# R-Split_Level_Shifter_1k_2k.net
KiCad netlist of a schematic drawn in EAGLE
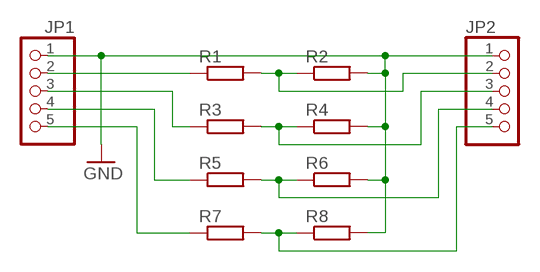
[diagram p0: schematic, sheet 1]

(export (version "E")
  (design (tool "Eeschema 10.0.6"))
  (components
    (comp (ref "JP1")
      (value "PINHD-1X5")
      (footprint "eagle-import:1X05")
      (libsource (lib "eagle-import") (part "PINHD-1X5"))
    )
    (comp (ref "JP2")
      (value "PINHD-1X5")
      (footprint "eagle-import:1X05")
      (libsource (lib "eagle-import") (part "PINHD-1X5"))
    )
    (comp (ref "R1")
      (value "R-EU_0207/7")
      (footprint "eagle-import:0207_7")
      (libsource (lib "eagle-import") (part "R-EU_0207/7"))
    )
    (comp (ref "R2")
      (value "R-EU_0207/7")
      (footprint "eagle-import:0207_7")
      (libsource (lib "eagle-import") (part "R-EU_0207/7"))
    )
    (comp (ref "R3")
      (value "R-EU_0207/7")
      (footprint "eagle-import:0207_7")
      (libsource (lib "eagle-import") (part "R-EU_0207/7"))
    )
    (comp (ref "R4")
      (value "R-EU_0207/7")
      (footprint "eagle-import:0207_7")
      (libsource (lib "eagle-import") (part "R-EU_0207/7"))
    )
    (comp (ref "R5")
      (value "R-EU_0207/7")
      (footprint "eagle-import:0207_7")
      (libsource (lib "eagle-import") (part "R-EU_0207/7"))
    )
    (comp (ref "R6")
      (value "R-EU_0207/7")
      (footprint "eagle-import:0207_7")
      (libsource (lib "eagle-import") (part "R-EU_0207/7"))
    )
    (comp (ref "R7")
      (value "R-EU_0207/7")
      (footprint "eagle-import:0207_7")
      (libsource (lib "eagle-import") (part "R-EU_0207/7"))
    )
    (comp (ref "R8")
      (value "R-EU_0207/7")
      (footprint "eagle-import:0207_7")
      (libsource (lib "eagle-import") (part "R-EU_0207/7"))
    )
  )
  (nets
    (net (code "1") (name "GND") (class "Default")
      (node (ref "JP1") (pin "1") (pinfunction "1_1") (pintype "passive"))
      (node (ref "JP2") (pin "1") (pinfunction "1_1") (pintype "passive"))
      (node (ref "R2") (pin "2") (pinfunction "2_2") (pintype "passive"))
      (node (ref "R4") (pin "2") (pinfunction "2_2") (pintype "passive"))
      (node (ref "R6") (pin "2") (pinfunction "2_2") (pintype "passive"))
      (node (ref "R8") (pin "2") (pinfunction "2_2") (pintype "passive"))
    )
    (net (code "2") (name "Net-(JP1-Pad2)") (class "Default")
      (node (ref "JP1") (pin "2") (pinfunction "2_2") (pintype "passive"))
      (node (ref "R1") (pin "1") (pinfunction "1_1") (pintype "passive"))
    )
    (net (code "3") (name "Net-(JP1-Pad3)") (class "Default")
      (node (ref "JP1") (pin "3") (pinfunction "3_3") (pintype "passive"))
      (node (ref "R3") (pin "1") (pinfunction "1_1") (pintype "passive"))
    )
    (net (code "4") (name "Net-(JP1-Pad4)") (class "Default")
      (node (ref "JP1") (pin "4") (pinfunction "4_4") (pintype "passive"))
      (node (ref "R5") (pin "1") (pinfunction "1_1") (pintype "passive"))
    )
    (net (code "5") (name "Net-(JP1-Pad5)") (class "Default")
      (node (ref "JP1") (pin "5") (pinfunction "5_5") (pintype "passive"))
      (node (ref "R7") (pin "1") (pinfunction "1_1") (pintype "passive"))
    )
    (net (code "6") (name "Net-(JP2-Pad2)") (class "Default")
      (node (ref "JP2") (pin "2") (pinfunction "2_2") (pintype "passive"))
      (node (ref "R1") (pin "2") (pinfunction "2_2") (pintype "passive"))
      (node (ref "R2") (pin "1") (pinfunction "1_1") (pintype "passive"))
    )
    (net (code "7") (name "Net-(JP2-Pad3)") (class "Default")
      (node (ref "JP2") (pin "3") (pinfunction "3_3") (pintype "passive"))
      (node (ref "R3") (pin "2") (pinfunction "2_2") (pintype "passive"))
      (node (ref "R4") (pin "1") (pinfunction "1_1") (pintype "passive"))
    )
    (net (code "8") (name "Net-(JP2-Pad4)") (class "Default")
      (node (ref "JP2") (pin "4") (pinfunction "4_4") (pintype "passive"))
      (node (ref "R5") (pin "2") (pinfunction "2_2") (pintype "passive"))
      (node (ref "R6") (pin "1") (pinfunction "1_1") (pintype "passive"))
    )
    (net (code "9") (name "Net-(JP2-Pad5)") (class "Default")
      (node (ref "JP2") (pin "5") (pinfunction "5_5") (pintype "passive"))
      (node (ref "R7") (pin "2") (pinfunction "2_2") (pintype "passive"))
      (node (ref "R8") (pin "1") (pinfunction "1_1") (pintype "passive"))
    )
  )
)
